# MercAp_PCB.net
KiCad netlist of a schematic drawn in Altium Designer
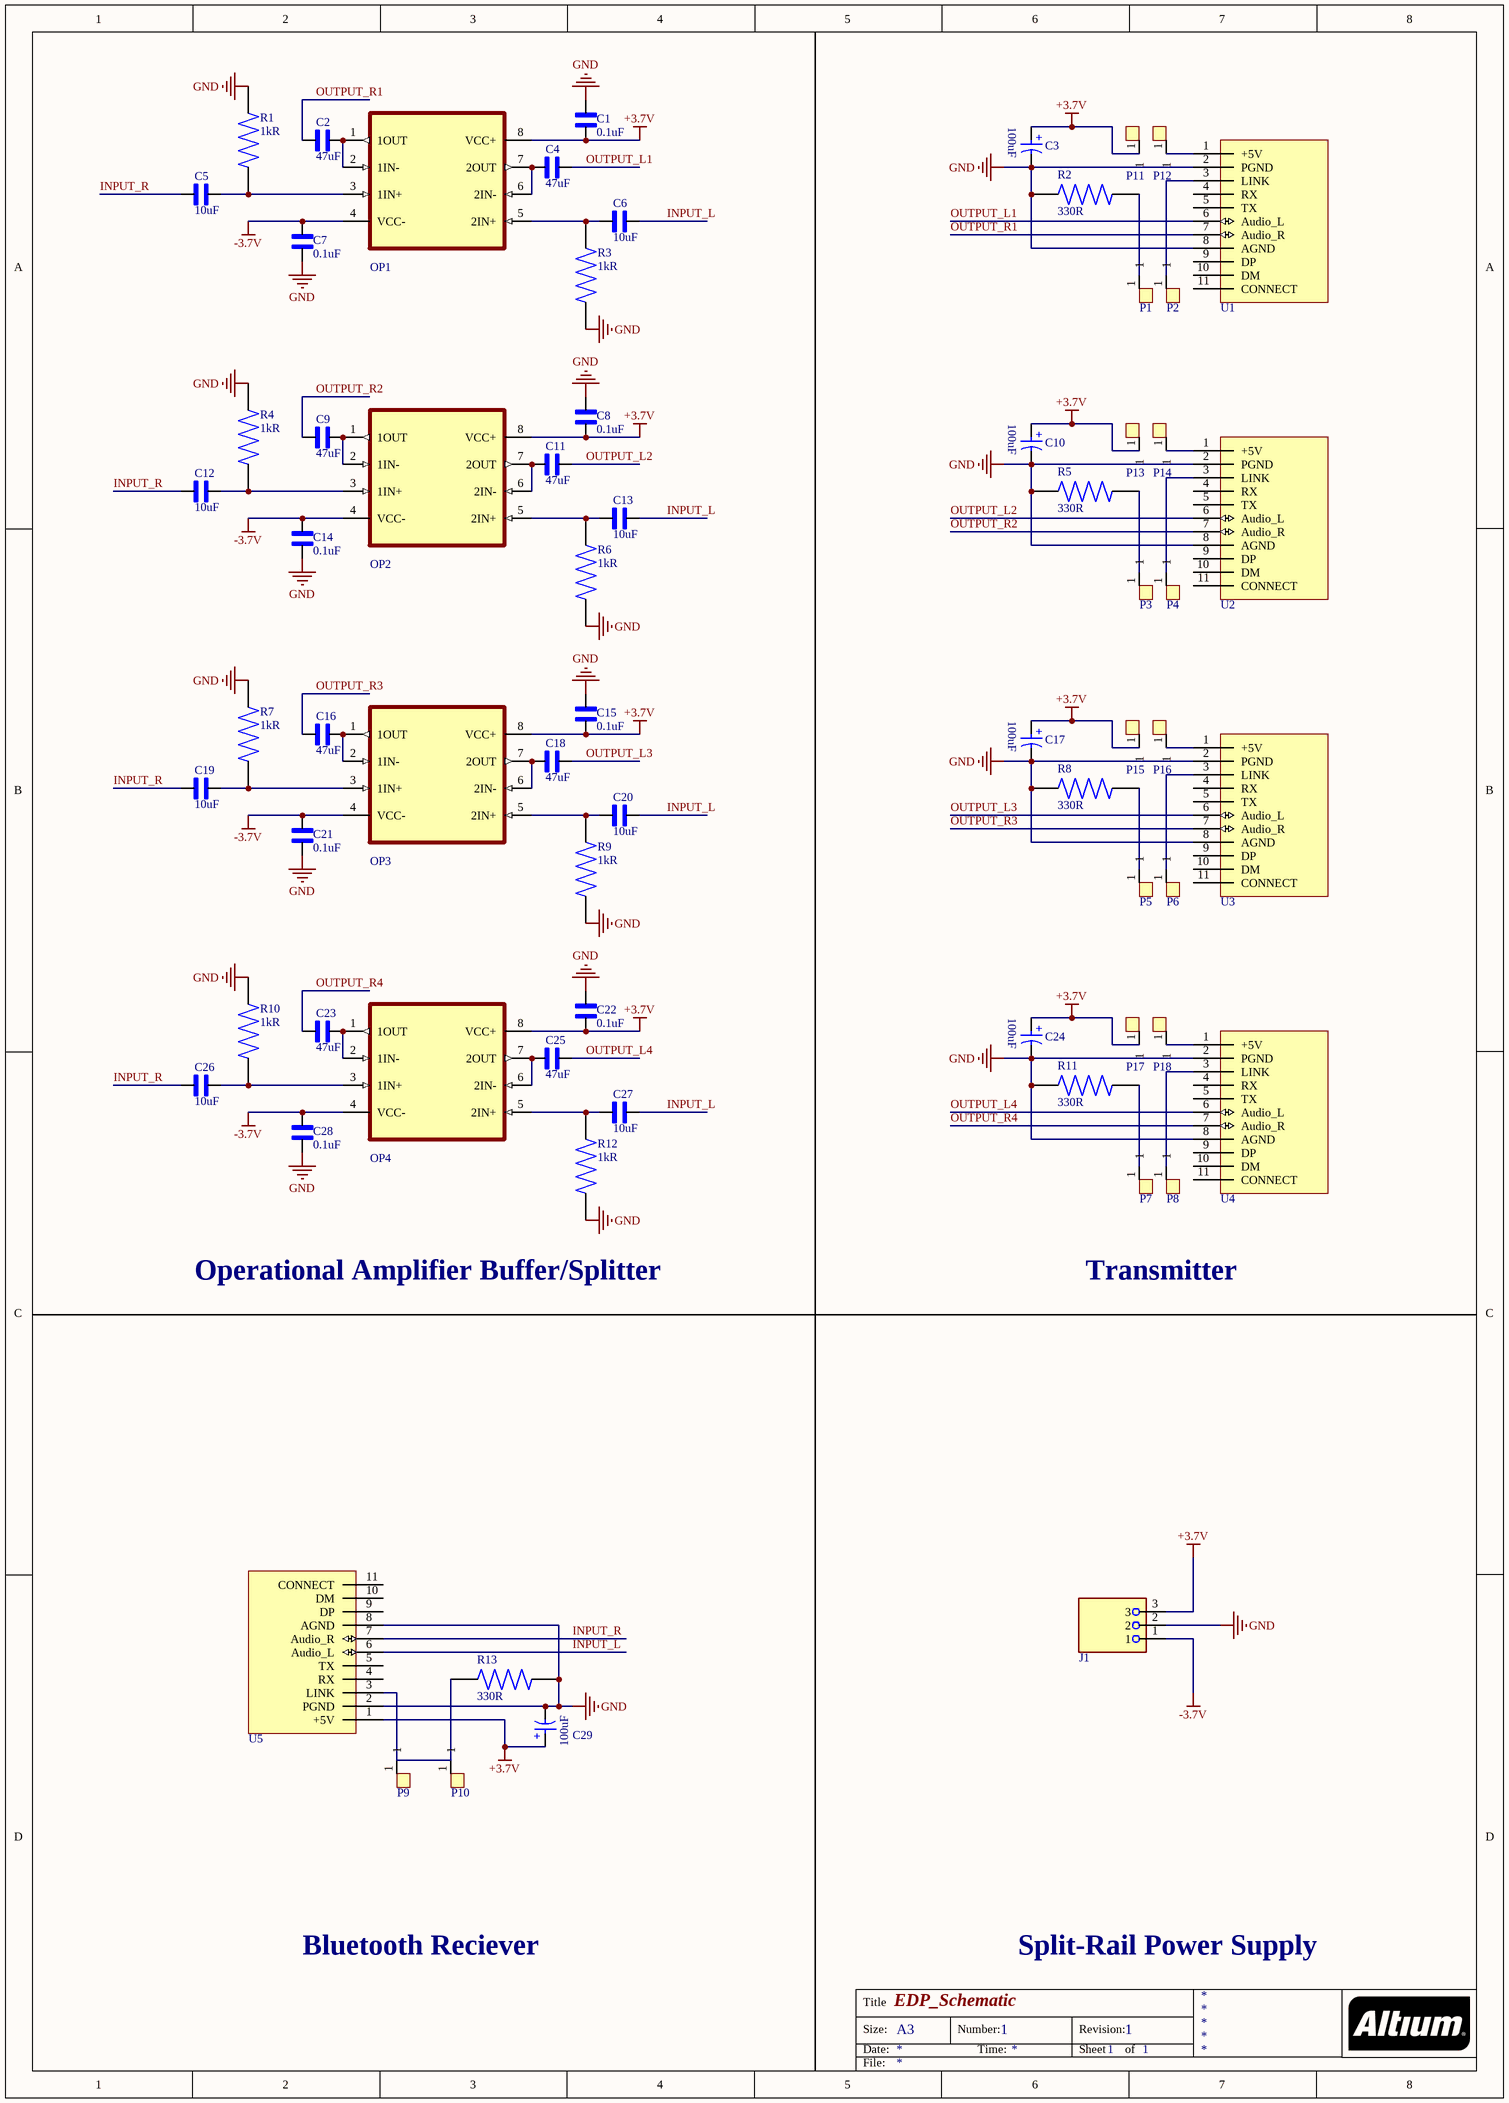
[diagram p0: MercAp PCB.SchDoc]

(export (version "E")
  (design (tool "Eeschema 10.0.6"))
  (components
    (comp (ref "C1")
      (value "0.1uF")
      (footprint "CAPC1005X55N")
      (fields
        (field (name "MANUFACTURER") "Samsung")
        (field (name "MANUFACTURER PART NUMBER") "CL05B104KP5NNNC")
      )
      (libsource (lib "EDP") (part "CL05B104KP5NNNC"))
    )
    (comp (ref "C2")
      (value "47uF")
      (footprint "CAPC2012X145N")
      (fields
        (field (name "MANUFACTURER") "Taiyo Yuden")
        (field (name "MANUFACTURER PART NUMBER") "JMK212BBJ476MG-T")
      )
      (libsource (lib "EDP") (part "JMK212BBJ476MG-T"))
    )
    (comp (ref "C3")
      (value "865080343009")
      (footprint "WCAP-ASLI_D6.3H5.5")
      (description "Aluminum Electrolytic Capacitor, Aluminum (wet)")
      (fields (field (name "MANUFACTURER") "Wurth Electronics"))
      (libsource (lib "EDP") (part "865080343009"))
    )
    (comp (ref "C4")
      (value "47uF")
      (footprint "CAPC2012X145N")
      (fields
        (field (name "MANUFACTURER") "Taiyo Yuden")
        (field (name "MANUFACTURER PART NUMBER") "JMK212BBJ476MG-T")
      )
      (libsource (lib "EDP") (part "JMK212BBJ476MG-T"))
    )
    (comp (ref "C5")
      (value "10uF")
      (footprint "CAPC2012X135N")
      (fields
        (field (name "MANUFACTURER") "Murata")
        (field (name "MANUFACTURER PART NUMBER") "GRM21BR61C106KE15K")
      )
      (libsource (lib "") (part "GRM21BR61C106KE15K_1"))
    )
    (comp (ref "C6")
      (value "10uF")
      (footprint "CAPC2012X135N")
      (fields
        (field (name "MANUFACTURER") "Murata")
        (field (name "MANUFACTURER PART NUMBER") "GRM21BR61C106KE15K")
      )
      (libsource (lib "EDP") (part "GRM21BR61C106KE15K"))
    )
    (comp (ref "C7")
      (value "0.1uF")
      (footprint "CAPC1005X55N")
      (fields
        (field (name "MANUFACTURER") "Samsung")
        (field (name "MANUFACTURER PART NUMBER") "CL05B104KP5NNNC")
      )
      (libsource (lib "EDP") (part "CL05B104KP5NNNC"))
    )
    (comp (ref "C8")
      (value "0.1uF")
      (footprint "CAPC1005X55N")
      (fields
        (field (name "MANUFACTURER") "Samsung")
        (field (name "MANUFACTURER PART NUMBER") "CL05B104KP5NNNC")
      )
      (libsource (lib "EDP") (part "CL05B104KP5NNNC"))
    )
    (comp (ref "C9")
      (value "47uF")
      (footprint "CAPC2012X145N")
      (fields
        (field (name "MANUFACTURER") "Taiyo Yuden")
        (field (name "MANUFACTURER PART NUMBER") "JMK212BBJ476MG-T")
      )
      (libsource (lib "EDP") (part "JMK212BBJ476MG-T"))
    )
    (comp (ref "C10")
      (value "865080343009")
      (footprint "WCAP-ASLI_D6.3H5.5")
      (description "Aluminum Electrolytic Capacitor, Aluminum (wet)")
      (fields (field (name "MANUFACTURER") "Wurth Electronics"))
      (libsource (lib "EDP") (part "865080343009"))
    )
    (comp (ref "C11")
      (value "47uF")
      (footprint "CAPC2012X145N")
      (fields
        (field (name "MANUFACTURER") "Taiyo Yuden")
        (field (name "MANUFACTURER PART NUMBER") "JMK212BBJ476MG-T")
      )
      (libsource (lib "EDP") (part "JMK212BBJ476MG-T"))
    )
    (comp (ref "C12")
      (value "10uF")
      (footprint "CAPC2012X135N")
      (fields
        (field (name "MANUFACTURER") "Murata")
        (field (name "MANUFACTURER PART NUMBER") "GRM21BR61C106KE15K")
      )
      (libsource (lib "") (part "GRM21BR61C106KE15K_1"))
    )
    (comp (ref "C13")
      (value "10uF")
      (footprint "CAPC2012X135N")
      (fields
        (field (name "MANUFACTURER") "Murata")
        (field (name "MANUFACTURER PART NUMBER") "GRM21BR61C106KE15K")
      )
      (libsource (lib "EDP") (part "GRM21BR61C106KE15K"))
    )
    (comp (ref "C14")
      (value "0.1uF")
      (footprint "CAPC1005X55N")
      (fields
        (field (name "MANUFACTURER") "Samsung")
        (field (name "MANUFACTURER PART NUMBER") "CL05B104KP5NNNC")
      )
      (libsource (lib "EDP") (part "CL05B104KP5NNNC"))
    )
    (comp (ref "C15")
      (value "0.1uF")
      (footprint "CAPC1005X55N")
      (fields
        (field (name "MANUFACTURER") "Samsung")
        (field (name "MANUFACTURER PART NUMBER") "CL05B104KP5NNNC")
      )
      (libsource (lib "EDP") (part "CL05B104KP5NNNC"))
    )
    (comp (ref "C16")
      (value "47uF")
      (footprint "CAPC2012X145N")
      (fields
        (field (name "MANUFACTURER") "Taiyo Yuden")
        (field (name "MANUFACTURER PART NUMBER") "JMK212BBJ476MG-T")
      )
      (libsource (lib "EDP") (part "JMK212BBJ476MG-T"))
    )
    (comp (ref "C17")
      (value "865080343009")
      (footprint "WCAP-ASLI_D6.3H5.5")
      (description "Aluminum Electrolytic Capacitor, Aluminum (wet)")
      (fields (field (name "MANUFACTURER") "Wurth Electronics"))
      (libsource (lib "EDP") (part "865080343009"))
    )
    (comp (ref "C18")
      (value "47uF")
      (footprint "CAPC2012X145N")
      (fields
        (field (name "MANUFACTURER") "Taiyo Yuden")
        (field (name "MANUFACTURER PART NUMBER") "JMK212BBJ476MG-T")
      )
      (libsource (lib "EDP") (part "JMK212BBJ476MG-T"))
    )
    (comp (ref "C19")
      (value "10uF")
      (footprint "CAPC2012X135N")
      (fields
        (field (name "MANUFACTURER") "Murata")
        (field (name "MANUFACTURER PART NUMBER") "GRM21BR61C106KE15K")
      )
      (libsource (lib "") (part "GRM21BR61C106KE15K_1"))
    )
    (comp (ref "C20")
      (value "10uF")
      (footprint "CAPC2012X135N")
      (fields
        (field (name "MANUFACTURER") "Murata")
        (field (name "MANUFACTURER PART NUMBER") "GRM21BR61C106KE15K")
      )
      (libsource (lib "EDP") (part "GRM21BR61C106KE15K"))
    )
    (comp (ref "C21")
      (value "0.1uF")
      (footprint "CAPC1005X55N")
      (fields
        (field (name "MANUFACTURER") "Samsung")
        (field (name "MANUFACTURER PART NUMBER") "CL05B104KP5NNNC")
      )
      (libsource (lib "EDP") (part "CL05B104KP5NNNC"))
    )
    (comp (ref "C22")
      (value "0.1uF")
      (footprint "CAPC1005X55N")
      (fields
        (field (name "MANUFACTURER") "Samsung")
        (field (name "MANUFACTURER PART NUMBER") "CL05B104KP5NNNC")
      )
      (libsource (lib "EDP") (part "CL05B104KP5NNNC"))
    )
    (comp (ref "C23")
      (value "47uF")
      (footprint "CAPC2012X145N")
      (fields
        (field (name "MANUFACTURER") "Taiyo Yuden")
        (field (name "MANUFACTURER PART NUMBER") "JMK212BBJ476MG-T")
      )
      (libsource (lib "EDP") (part "JMK212BBJ476MG-T"))
    )
    (comp (ref "C24")
      (value "865080343009")
      (footprint "WCAP-ASLI_D6.3H5.5")
      (description "Aluminum Electrolytic Capacitor, Aluminum (wet)")
      (fields (field (name "MANUFACTURER") "Wurth Electronics"))
      (libsource (lib "EDP") (part "865080343009"))
    )
    (comp (ref "C25")
      (value "47uF")
      (footprint "CAPC2012X145N")
      (fields
        (field (name "MANUFACTURER") "Taiyo Yuden")
        (field (name "MANUFACTURER PART NUMBER") "JMK212BBJ476MG-T")
      )
      (libsource (lib "EDP") (part "JMK212BBJ476MG-T"))
    )
    (comp (ref "C26")
      (value "10uF")
      (footprint "CAPC2012X135N")
      (fields
        (field (name "MANUFACTURER") "Murata")
        (field (name "MANUFACTURER PART NUMBER") "GRM21BR61C106KE15K")
      )
      (libsource (lib "") (part "GRM21BR61C106KE15K_1"))
    )
    (comp (ref "C27")
      (value "10uF")
      (footprint "CAPC2012X135N")
      (fields
        (field (name "MANUFACTURER") "Murata")
        (field (name "MANUFACTURER PART NUMBER") "GRM21BR61C106KE15K")
      )
      (libsource (lib "EDP") (part "GRM21BR61C106KE15K"))
    )
    (comp (ref "C28")
      (value "0.1uF")
      (footprint "CAPC1005X55N")
      (fields
        (field (name "MANUFACTURER") "Samsung")
        (field (name "MANUFACTURER PART NUMBER") "CL05B104KP5NNNC")
      )
      (libsource (lib "EDP") (part "CL05B104KP5NNNC"))
    )
    (comp (ref "C29")
      (value "865080343009")
      (footprint "WCAP-ASLI_D6.3H5.5")
      (description "Aluminum Electrolytic Capacitor, Aluminum (wet)")
      (fields (field (name "MANUFACTURER") "Wurth Electronics"))
      (libsource (lib "EDP") (part "865080343009"))
    )
    (comp (ref "J1")
      (value "1935174")
      (footprint "PHOENIX_1935174")
      (description "Barrier Strip Terminal Block, 17.5A, 1.5mm2, 1 Row(s), 1 Deck(s)")
      (fields (field (name "MANUFACTURER") "Phoenix Contact") (field (name "SAFETY APPROVAL") "UL"))
      (libsource (lib "EDP") (part "1935174"))
    )
    (comp (ref "OP1")
      (value "NE5532DR")
      (footprint "SOIC127P599X175-8N")
      (description "Operational Amplifier, 2 Func, 5000uV Offset-Max, BIPolar, PDSO8")
      (fields (field (name "MANUFACTURER") "Texas Instruments"))
      (libsource (lib "EDP") (part "NE5532DR"))
    )
    (comp (ref "OP2")
      (value "NE5532DR")
      (footprint "SOIC127P599X175-8N")
      (description "Operational Amplifier, 2 Func, 5000uV Offset-Max, BIPolar, PDSO8")
      (fields (field (name "MANUFACTURER") "Texas Instruments"))
      (libsource (lib "EDP") (part "NE5532DR"))
    )
    (comp (ref "OP3")
      (value "NE5532DR")
      (footprint "SOIC127P599X175-8N")
      (description "Operational Amplifier, 2 Func, 5000uV Offset-Max, BIPolar, PDSO8")
      (fields (field (name "MANUFACTURER") "Texas Instruments"))
      (libsource (lib "EDP") (part "NE5532DR"))
    )
    (comp (ref "OP4")
      (value "NE5532DR")
      (footprint "SOIC127P599X175-8N")
      (description "Operational Amplifier, 2 Func, 5000uV Offset-Max, BIPolar, PDSO8")
      (fields (field (name "MANUFACTURER") "Texas Instruments"))
      (libsource (lib "EDP") (part "NE5532DR"))
    )
    (comp (ref "P1")
      (value "LED_PAD")
      (footprint "SolderWirePad_1x01_SMD_5x10mm")
      (libsource (lib "EDP") (part "LED_PAD"))
    )
    (comp (ref "P2")
      (value "LED_PAD")
      (footprint "SolderWirePad_1x01_SMD_5x10mm")
      (libsource (lib "EDP") (part "LED_PAD"))
    )
    (comp (ref "P3")
      (value "LED_PAD")
      (footprint "SolderWirePad_1x01_SMD_5x10mm")
      (libsource (lib "EDP") (part "LED_PAD"))
    )
    (comp (ref "P4")
      (value "LED_PAD")
      (footprint "SolderWirePad_1x01_SMD_5x10mm")
      (libsource (lib "EDP") (part "LED_PAD"))
    )
    (comp (ref "P5")
      (value "LED_PAD")
      (footprint "SolderWirePad_1x01_SMD_5x10mm")
      (libsource (lib "EDP") (part "LED_PAD"))
    )
    (comp (ref "P6")
      (value "LED_PAD")
      (footprint "SolderWirePad_1x01_SMD_5x10mm")
      (libsource (lib "EDP") (part "LED_PAD"))
    )
    (comp (ref "P7")
      (value "LED_PAD")
      (footprint "SolderWirePad_1x01_SMD_5x10mm")
      (libsource (lib "EDP") (part "LED_PAD"))
    )
    (comp (ref "P8")
      (value "LED_PAD")
      (footprint "SolderWirePad_1x01_SMD_5x10mm")
      (libsource (lib "EDP") (part "LED_PAD"))
    )
    (comp (ref "P9")
      (value "LED_PAD")
      (footprint "SolderWirePad_1x01_SMD_5x10mm")
      (libsource (lib "EDP") (part "LED_PAD"))
    )
    (comp (ref "P10")
      (value "LED_PAD")
      (footprint "SolderWirePad_1x01_SMD_5x10mm")
      (libsource (lib "EDP") (part "LED_PAD"))
    )
    (comp (ref "P11")
      (value "LED_PAD")
      (footprint "SolderWirePad_1x01_SMD_5x10mm")
      (libsource (lib "") (part "LED_PAD_1"))
    )
    (comp (ref "P12")
      (value "LED_PAD")
      (footprint "SolderWirePad_1x01_SMD_5x10mm")
      (libsource (lib "") (part "LED_PAD_1"))
    )
    (comp (ref "P13")
      (value "LED_PAD")
      (footprint "SolderWirePad_1x01_SMD_5x10mm")
      (libsource (lib "") (part "LED_PAD_1"))
    )
    (comp (ref "P14")
      (value "LED_PAD")
      (footprint "SolderWirePad_1x01_SMD_5x10mm")
      (libsource (lib "") (part "LED_PAD_1"))
    )
    (comp (ref "P15")
      (value "LED_PAD")
      (footprint "SolderWirePad_1x01_SMD_5x10mm")
      (libsource (lib "") (part "LED_PAD_1"))
    )
    (comp (ref "P16")
      (value "LED_PAD")
      (footprint "SolderWirePad_1x01_SMD_5x10mm")
      (libsource (lib "") (part "LED_PAD_1"))
    )
    (comp (ref "P17")
      (value "LED_PAD")
      (footprint "SolderWirePad_1x01_SMD_5x10mm")
      (libsource (lib "") (part "LED_PAD_1"))
    )
    (comp (ref "P18")
      (value "LED_PAD")
      (footprint "SolderWirePad_1x01_SMD_5x10mm")
      (libsource (lib "") (part "LED_PAD_1"))
    )
    (comp (ref "R1")
      (value "1kR")
      (footprint "RESC1508X55N")
      (fields
        (field (name "MANUFACTURER") "Stackpole Electronics")
        (field (name "MANUFACTURER PART NUMBER") "RMCF0603FT1K00")
        (field (name "TOLERANCE") "1%")
      )
      (libsource (lib "EDP") (part "RMCF0603FT1K00"))
    )
    (comp (ref "R2")
      (value "330R")
      (footprint "RESC1608X55N")
      (fields
        (field (name "MANUFACTURER") "Yageo")
        (field (name "MANUFACTURER PART NUMBER") "RC0603JR-07330RL")
        (field (name "TOLERANCE") "5%")
      )
      (libsource (lib "EDP") (part "RC0603JR-07330RL"))
    )
    (comp (ref "R3")
      (value "1kR")
      (footprint "RESC1508X55N")
      (fields
        (field (name "MANUFACTURER") "Stackpole Electronics")
        (field (name "MANUFACTURER PART NUMBER") "RMCF0603FT1K00")
        (field (name "TOLERANCE") "1%")
      )
      (libsource (lib "EDP") (part "RMCF0603FT1K00"))
    )
    (comp (ref "R4")
      (value "1kR")
      (footprint "RESC1508X55N")
      (fields
        (field (name "MANUFACTURER") "Stackpole Electronics")
        (field (name "MANUFACTURER PART NUMBER") "RMCF0603FT1K00")
        (field (name "TOLERANCE") "1%")
      )
      (libsource (lib "EDP") (part "RMCF0603FT1K00"))
    )
    (comp (ref "R5")
      (value "330R")
      (footprint "RESC1608X55N")
      (fields
        (field (name "MANUFACTURER") "Yageo")
        (field (name "MANUFACTURER PART NUMBER") "RC0603JR-07330RL")
        (field (name "TOLERANCE") "5%")
      )
      (libsource (lib "EDP") (part "RC0603JR-07330RL"))
    )
    (comp (ref "R6")
      (value "1kR")
      (footprint "RESC1508X55N")
      (fields
        (field (name "MANUFACTURER") "Stackpole Electronics")
        (field (name "MANUFACTURER PART NUMBER") "RMCF0603FT1K00")
        (field (name "TOLERANCE") "1%")
      )
      (libsource (lib "EDP") (part "RMCF0603FT1K00"))
    )
    (comp (ref "R7")
      (value "1kR")
      (footprint "RESC1508X55N")
      (fields
        (field (name "MANUFACTURER") "Stackpole Electronics")
        (field (name "MANUFACTURER PART NUMBER") "RMCF0603FT1K00")
        (field (name "TOLERANCE") "1%")
      )
      (libsource (lib "EDP") (part "RMCF0603FT1K00"))
    )
    (comp (ref "R8")
      (value "330R")
      (footprint "RESC1608X55N")
      (fields
        (field (name "MANUFACTURER") "Yageo")
        (field (name "MANUFACTURER PART NUMBER") "RC0603JR-07330RL")
        (field (name "TOLERANCE") "5%")
      )
      (libsource (lib "EDP") (part "RC0603JR-07330RL"))
    )
    (comp (ref "R9")
      (value "1kR")
      (footprint "RESC1508X55N")
      (fields
        (field (name "MANUFACTURER") "Stackpole Electronics")
        (field (name "MANUFACTURER PART NUMBER") "RMCF0603FT1K00")
        (field (name "TOLERANCE") "1%")
      )
      (libsource (lib "EDP") (part "RMCF0603FT1K00"))
    )
    (comp (ref "R10")
      (value "1kR")
      (footprint "RESC1508X55N")
      (fields
        (field (name "MANUFACTURER") "Stackpole Electronics")
        (field (name "MANUFACTURER PART NUMBER") "RMCF0603FT1K00")
        (field (name "TOLERANCE") "1%")
      )
      (libsource (lib "EDP") (part "RMCF0603FT1K00"))
    )
    (comp (ref "R11")
      (value "330R")
      (footprint "RESC1608X55N")
      (fields
        (field (name "MANUFACTURER") "Yageo")
        (field (name "MANUFACTURER PART NUMBER") "RC0603JR-07330RL")
        (field (name "TOLERANCE") "5%")
      )
      (libsource (lib "EDP") (part "RC0603JR-07330RL"))
    )
    (comp (ref "R12")
      (value "1kR")
      (footprint "RESC1508X55N")
      (fields
        (field (name "MANUFACTURER") "Stackpole Electronics")
        (field (name "MANUFACTURER PART NUMBER") "RMCF0603FT1K00")
        (field (name "TOLERANCE") "1%")
      )
      (libsource (lib "EDP") (part "RMCF0603FT1K00"))
    )
    (comp (ref "R13")
      (value "330R")
      (footprint "RESC1608X55N")
      (fields
        (field (name "MANUFACTURER") "Yageo")
        (field (name "MANUFACTURER PART NUMBER") "RC0603JR-07330RL")
        (field (name "TOLERANCE") "5%")
      )
      (libsource (lib "EDP") (part "RC0603JR-07330RL"))
    )
    (comp (ref "U1")
      (value "KCX_BT_v1.4")
      (footprint "kcx_bt_emitter_foot")
      (libsource (lib "EDP") (part "KCX_BT_v1.4"))
    )
    (comp (ref "U2")
      (value "KCX_BT_v1.4")
      (footprint "kcx_bt_emitter_foot")
      (libsource (lib "EDP") (part "KCX_BT_v1.4"))
    )
    (comp (ref "U3")
      (value "KCX_BT_v1.4")
      (footprint "kcx_bt_emitter_foot")
      (libsource (lib "EDP") (part "KCX_BT_v1.4"))
    )
    (comp (ref "U4")
      (value "KCX_BT_v1.4")
      (footprint "kcx_bt_emitter_foot")
      (libsource (lib "EDP") (part "KCX_BT_v1.4"))
    )
    (comp (ref "U5")
      (value "KCX_BT_v1.4")
      (footprint "kcx_bt_emitter_foot")
      (libsource (lib "") (part "KCX_BT_v1.4_1"))
    )
  )
  (nets
    (net (code "1") (name "+3.7V") (class "Default")
      (node (ref "C1") (pin "1") (pinfunction "1_1") (pintype "passive"))
      (node (ref "C10") (pin "1") (pinfunction "P_1") (pintype "passive"))
      (node (ref "C15") (pin "1") (pinfunction "1_1") (pintype "passive"))
      (node (ref "C17") (pin "1") (pinfunction "P_1") (pintype "passive"))
      (node (ref "C22") (pin "1") (pinfunction "1_1") (pintype "passive"))
      (node (ref "C24") (pin "1") (pinfunction "P_1") (pintype "passive"))
      (node (ref "C29") (pin "1") (pinfunction "P_1") (pintype "passive"))
      (node (ref "C3") (pin "1") (pinfunction "P_1") (pintype "passive"))
      (node (ref "C8") (pin "1") (pinfunction "1_1") (pintype "passive"))
      (node (ref "J1") (pin "3") (pinfunction "3_3") (pintype "passive"))
      (node (ref "OP1") (pin "8") (pinfunction "VCC+_8") (pintype "power_in"))
      (node (ref "OP2") (pin "8") (pinfunction "VCC+_8") (pintype "power_in"))
      (node (ref "OP3") (pin "8") (pinfunction "VCC+_8") (pintype "power_in"))
      (node (ref "OP4") (pin "8") (pinfunction "VCC+_8") (pintype "power_in"))
      (node (ref "U5") (pin "1") (pinfunction "+5V_1") (pintype "power_in"))
    )
    (net (code "2") (name "-3.7V") (class "Default")
      (node (ref "C14") (pin "2") (pinfunction "2_2") (pintype "passive"))
      (node (ref "C21") (pin "2") (pinfunction "2_2") (pintype "passive"))
      (node (ref "C28") (pin "2") (pinfunction "2_2") (pintype "passive"))
      (node (ref "C7") (pin "2") (pinfunction "2_2") (pintype "passive"))
      (node (ref "J1") (pin "1") (pinfunction "1_1") (pintype "passive"))
      (node (ref "OP1") (pin "4") (pinfunction "VCC-_4") (pintype "power_in"))
      (node (ref "OP2") (pin "4") (pinfunction "VCC-_4") (pintype "power_in"))
      (node (ref "OP3") (pin "4") (pinfunction "VCC-_4") (pintype "power_in"))
      (node (ref "OP4") (pin "4") (pinfunction "VCC-_4") (pintype "power_in"))
    )
    (net (code "3") (name "/INPUT_L") (class "Default")
      (node (ref "C13") (pin "1") (pinfunction "1_1") (pintype "passive"))
      (node (ref "C20") (pin "1") (pinfunction "1_1") (pintype "passive"))
      (node (ref "C27") (pin "1") (pinfunction "1_1") (pintype "passive"))
      (node (ref "C6") (pin "1") (pinfunction "1_1") (pintype "passive"))
      (node (ref "U5") (pin "6") (pinfunction "Audio_L_6") (pintype "bidirectional"))
    )
    (net (code "4") (name "/INPUT_R") (class "Default")
      (node (ref "C12") (pin "1") (pinfunction "1_1") (pintype "passive"))
      (node (ref "C19") (pin "1") (pinfunction "1_1") (pintype "passive"))
      (node (ref "C26") (pin "1") (pinfunction "1_1") (pintype "passive"))
      (node (ref "C5") (pin "1") (pinfunction "1_1") (pintype "passive"))
      (node (ref "U5") (pin "7") (pinfunction "Audio_R_7") (pintype "bidirectional"))
    )
    (net (code "5") (name "/OUTPUT_L1") (class "Default")
      (node (ref "C4") (pin "2") (pinfunction "2_2") (pintype "passive"))
      (node (ref "U1") (pin "6") (pinfunction "Audio_L_6") (pintype "bidirectional"))
    )
    (net (code "6") (name "/OUTPUT_L2") (class "Default")
      (node (ref "C11") (pin "2") (pinfunction "2_2") (pintype "passive"))
      (node (ref "U2") (pin "6") (pinfunction "Audio_L_6") (pintype "bidirectional"))
    )
    (net (code "7") (name "/OUTPUT_L3") (class "Default")
      (node (ref "C18") (pin "2") (pinfunction "2_2") (pintype "passive"))
      (node (ref "U3") (pin "6") (pinfunction "Audio_L_6") (pintype "bidirectional"))
    )
    (net (code "8") (name "/OUTPUT_L4") (class "Default")
      (node (ref "C25") (pin "2") (pinfunction "2_2") (pintype "passive"))
      (node (ref "U4") (pin "6") (pinfunction "Audio_L_6") (pintype "bidirectional"))
    )
    (net (code "9") (name "/OUTPUT_R1") (class "Default")
      (node (ref "C2") (pin "1") (pinfunction "1_1") (pintype "passive"))
      (node (ref "U1") (pin "7") (pinfunction "Audio_R_7") (pintype "bidirectional"))
    )
    (net (code "10") (name "/OUTPUT_R2") (class "Default")
      (node (ref "C9") (pin "1") (pinfunction "1_1") (pintype "passive"))
      (node (ref "U2") (pin "7") (pinfunction "Audio_R_7") (pintype "bidirectional"))
    )
    (net (code "11") (name "/OUTPUT_R3") (class "Default")
      (node (ref "C16") (pin "1") (pinfunction "1_1") (pintype "passive"))
      (node (ref "U3") (pin "7") (pinfunction "Audio_R_7") (pintype "bidirectional"))
    )
    (net (code "12") (name "/OUTPUT_R4") (class "Default")
      (node (ref "C23") (pin "1") (pinfunction "1_1") (pintype "passive"))
      (node (ref "U4") (pin "7") (pinfunction "Audio_R_7") (pintype "bidirectional"))
    )
    (net (code "13") (name "GND") (class "Default")
      (node (ref "C1") (pin "2") (pinfunction "2_2") (pintype "passive"))
      (node (ref "C10") (pin "2") (pinfunction "N_2") (pintype "passive"))
      (node (ref "C14") (pin "1") (pinfunction "1_1") (pintype "passive"))
      (node (ref "C15") (pin "2") (pinfunction "2_2") (pintype "passive"))
      (node (ref "C17") (pin "2") (pinfunction "N_2") (pintype "passive"))
      (node (ref "C21") (pin "1") (pinfunction "1_1") (pintype "passive"))
      (node (ref "C22") (pin "2") (pinfunction "2_2") (pintype "passive"))
      (node (ref "C24") (pin "2") (pinfunction "N_2") (pintype "passive"))
      (node (ref "C28") (pin "1") (pinfunction "1_1") (pintype "passive"))
      (node (ref "C29") (pin "2") (pinfunction "N_2") (pintype "passive"))
      (node (ref "C3") (pin "2") (pinfunction "N_2") (pintype "passive"))
      (node (ref "C7") (pin "1") (pinfunction "1_1") (pintype "passive"))
      (node (ref "C8") (pin "2") (pinfunction "2_2") (pintype "passive"))
      (node (ref "J1") (pin "2") (pinfunction "2_2") (pintype "passive"))
      (node (ref "R1") (pin "1") (pinfunction "1_1") (pintype "passive"))
      (node (ref "R10") (pin "1") (pinfunction "1_1") (pintype "passive"))
      (node (ref "R11") (pin "1") (pinfunction "1_1") (pintype "passive"))
      (node (ref "R12") (pin "1") (pinfunction "1_1") (pintype "passive"))
      (node (ref "R13") (pin "1") (pinfunction "1_1") (pintype "passive"))
      (node (ref "R2") (pin "1") (pinfunction "1_1") (pintype "passive"))
      (node (ref "R3") (pin "1") (pinfunction "1_1") (pintype "passive"))
      (node (ref "R4") (pin "1") (pinfunction "1_1") (pintype "passive"))
      (node (ref "R5") (pin "1") (pinfunction "1_1") (pintype "passive"))
      (node (ref "R6") (pin "1") (pinfunction "1_1") (pintype "passive"))
      (node (ref "R7") (pin "1") (pinfunction "1_1") (pintype "passive"))
      (node (ref "R8") (pin "1") (pinfunction "1_1") (pintype "passive"))
      (node (ref "R9") (pin "1") (pinfunction "1_1") (pintype "passive"))
      (node (ref "U1") (pin "2") (pinfunction "PGND_2") (pintype "power_in"))
      (node (ref "U1") (pin "8") (pinfunction "AGND_8") (pintype "power_in"))
      (node (ref "U2") (pin "2") (pinfunction "PGND_2") (pintype "power_in"))
      (node (ref "U2") (pin "8") (pinfunction "AGND_8") (pintype "power_in"))
      (node (ref "U3") (pin "2") (pinfunction "PGND_2") (pintype "power_in"))
      (node (ref "U3") (pin "8") (pinfunction "AGND_8") (pintype "power_in"))
      (node (ref "U4") (pin "2") (pinfunction "PGND_2") (pintype "power_in"))
      (node (ref "U4") (pin "8") (pinfunction "AGND_8") (pintype "power_in"))
      (node (ref "U5") (pin "2") (pinfunction "PGND_2") (pintype "power_in"))
      (node (ref "U5") (pin "8") (pinfunction "AGND_8") (pintype "power_in"))
    )
    (net (code "14") (name "Net-(OP1-1IN+)") (class "Default")
      (node (ref "C5") (pin "2") (pinfunction "2_2") (pintype "passive"))
      (node (ref "OP1") (pin "3") (pinfunction "1IN+_3") (pintype "input"))
      (node (ref "R1") (pin "2") (pinfunction "2_2") (pintype "passive"))
    )
    (net (code "15") (name "Net-(OP1-1IN-)") (class "Default")
      (node (ref "C2") (pin "2") (pinfunction "2_2") (pintype "passive"))
      (node (ref "OP1") (pin "1") (pinfunction "1OUT_1") (pintype "output"))
      (node (ref "OP1") (pin "2") (pinfunction "1IN-_2") (pintype "input"))
    )
    (net (code "16") (name "Net-(OP1-2IN+)") (class "Default")
      (node (ref "C6") (pin "2") (pinfunction "2_2") (pintype "passive"))
      (node (ref "OP1") (pin "5") (pinfunction "2IN+_5") (pintype "input"))
      (node (ref "R3") (pin "2") (pinfunction "2_2") (pintype "passive"))
    )
    (net (code "17") (name "Net-(OP1-2IN-)") (class "Default")
      (node (ref "C4") (pin "1") (pinfunction "1_1") (pintype "passive"))
      (node (ref "OP1") (pin "6") (pinfunction "2IN-_6") (pintype "input"))
      (node (ref "OP1") (pin "7") (pinfunction "2OUT_7") (pintype "output"))
    )
    (net (code "18") (name "Net-(OP2-1IN+)") (class "Default")
      (node (ref "C12") (pin "2") (pinfunction "2_2") (pintype "passive"))
      (node (ref "OP2") (pin "3") (pinfunction "1IN+_3") (pintype "input"))
      (node (ref "R4") (pin "2") (pinfunction "2_2") (pintype "passive"))
    )
    (net (code "19") (name "Net-(OP2-1IN-)") (class "Default")
      (node (ref "C9") (pin "2") (pinfunction "2_2") (pintype "passive"))
      (node (ref "OP2") (pin "1") (pinfunction "1OUT_1") (pintype "output"))
      (node (ref "OP2") (pin "2") (pinfunction "1IN-_2") (pintype "input"))
    )
    (net (code "20") (name "Net-(OP2-2IN+)") (class "Default")
      (node (ref "C13") (pin "2") (pinfunction "2_2") (pintype "passive"))
      (node (ref "OP2") (pin "5") (pinfunction "2IN+_5") (pintype "input"))
      (node (ref "R6") (pin "2") (pinfunction "2_2") (pintype "passive"))
    )
    (net (code "21") (name "Net-(OP2-2IN-)") (class "Default")
      (node (ref "C11") (pin "1") (pinfunction "1_1") (pintype "passive"))
      (node (ref "OP2") (pin "6") (pinfunction "2IN-_6") (pintype "input"))
      (node (ref "OP2") (pin "7") (pinfunction "2OUT_7") (pintype "output"))
    )
    (net (code "22") (name "Net-(OP3-1IN+)") (class "Default")
      (node (ref "C19") (pin "2") (pinfunction "2_2") (pintype "passive"))
      (node (ref "OP3") (pin "3") (pinfunction "1IN+_3") (pintype "input"))
      (node (ref "R7") (pin "2") (pinfunction "2_2") (pintype "passive"))
    )
    (net (code "23") (name "Net-(OP3-1IN-)") (class "Default")
      (node (ref "C16") (pin "2") (pinfunction "2_2") (pintype "passive"))
      (node (ref "OP3") (pin "1") (pinfunction "1OUT_1") (pintype "output"))
      (node (ref "OP3") (pin "2") (pinfunction "1IN-_2") (pintype "input"))
    )
    (net (code "24") (name "Net-(OP3-2IN+)") (class "Default")
      (node (ref "C20") (pin "2") (pinfunction "2_2") (pintype "passive"))
      (node (ref "OP3") (pin "5") (pinfunction "2IN+_5") (pintype "input"))
      (node (ref "R9") (pin "2") (pinfunction "2_2") (pintype "passive"))
    )
    (net (code "25") (name "Net-(OP3-2IN-)") (class "Default")
      (node (ref "C18") (pin "1") (pinfunction "1_1") (pintype "passive"))
      (node (ref "OP3") (pin "6") (pinfunction "2IN-_6") (pintype "input"))
      (node (ref "OP3") (pin "7") (pinfunction "2OUT_7") (pintype "output"))
    )
    (net (code "26") (name "Net-(OP4-1IN+)") (class "Default")
      (node (ref "C26") (pin "2") (pinfunction "2_2") (pintype "passive"))
      (node (ref "OP4") (pin "3") (pinfunction "1IN+_3") (pintype "input"))
      (node (ref "R10") (pin "2") (pinfunction "2_2") (pintype "passive"))
    )
    (net (code "27") (name "Net-(OP4-1IN-)") (class "Default")
      (node (ref "C23") (pin "2") (pinfunction "2_2") (pintype "passive"))
      (node (ref "OP4") (pin "1") (pinfunction "1OUT_1") (pintype "output"))
      (node (ref "OP4") (pin "2") (pinfunction "1IN-_2") (pintype "input"))
    )
    (net (code "28") (name "Net-(OP4-2IN+)") (class "Default")
      (node (ref "C27") (pin "2") (pinfunction "2_2") (pintype "passive"))
      (node (ref "OP4") (pin "5") (pinfunction "2IN+_5") (pintype "input"))
      (node (ref "R12") (pin "2") (pinfunction "2_2") (pintype "passive"))
    )
    (net (code "29") (name "Net-(OP4-2IN-)") (class "Default")
      (node (ref "C25") (pin "1") (pinfunction "1_1") (pintype "passive"))
      (node (ref "OP4") (pin "6") (pinfunction "2IN-_6") (pintype "input"))
      (node (ref "OP4") (pin "7") (pinfunction "2OUT_7") (pintype "output"))
    )
    (net (code "30") (name "Net-(U5-LINK)") (class "Default")
      (node (ref "R13") (pin "2") (pinfunction "2_2") (pintype "passive"))
      (node (ref "U5") (pin "3") (pinfunction "LINK_3") (pintype "passive"))
    )
    (net (code "31") (name "unconnected-(P1-Pad1)") (class "Default")
      (node (ref "P1") (pin "1") (pinfunction "1_1") (pintype "passive"))
    )
    (net (code "32") (name "unconnected-(P2-Pad1)") (class "Default")
      (node (ref "P2") (pin "1") (pinfunction "1_1") (pintype "passive"))
    )
    (net (code "33") (name "unconnected-(P3-Pad1)") (class "Default")
      (node (ref "P3") (pin "1") (pinfunction "1_1") (pintype "passive"))
    )
    (net (code "34") (name "unconnected-(P4-Pad1)") (class "Default")
      (node (ref "P4") (pin "1") (pinfunction "1_1") (pintype "passive"))
    )
    (net (code "35") (name "unconnected-(P5-Pad1)") (class "Default")
      (node (ref "P5") (pin "1") (pinfunction "1_1") (pintype "passive"))
    )
    (net (code "36") (name "unconnected-(P6-Pad1)") (class "Default")
      (node (ref "P6") (pin "1") (pinfunction "1_1") (pintype "passive"))
    )
    (net (code "37") (name "unconnected-(P7-Pad1)") (class "Default")
      (node (ref "P7") (pin "1") (pinfunction "1_1") (pintype "passive"))
    )
    (net (code "38") (name "unconnected-(P8-Pad1)") (class "Default")
      (node (ref "P8") (pin "1") (pinfunction "1_1") (pintype "passive"))
    )
    (net (code "39") (name "unconnected-(P9-Pad1)") (class "Default")
      (node (ref "P9") (pin "1") (pinfunction "1_1") (pintype "passive"))
    )
    (net (code "40") (name "unconnected-(P10-Pad1)") (class "Default")
      (node (ref "P10") (pin "1") (pinfunction "1_1") (pintype "passive"))
    )
    (net (code "41") (name "unconnected-(P11-Pad1)") (class "Default")
      (node (ref "P11") (pin "1") (pinfunction "1_1") (pintype "passive"))
    )
    (net (code "42") (name "unconnected-(P12-Pad1)") (class "Default")
      (node (ref "P12") (pin "1") (pinfunction "1_1") (pintype "passive"))
    )
    (net (code "43") (name "unconnected-(P13-Pad1)") (class "Default")
      (node (ref "P13") (pin "1") (pinfunction "1_1") (pintype "passive"))
    )
    (net (code "44") (name "unconnected-(P14-Pad1)") (class "Default")
      (node (ref "P14") (pin "1") (pinfunction "1_1") (pintype "passive"))
    )
    (net (code "45") (name "unconnected-(P15-Pad1)") (class "Default")
      (node (ref "P15") (pin "1") (pinfunction "1_1") (pintype "passive"))
    )
    (net (code "46") (name "unconnected-(P16-Pad1)") (class "Default")
      (node (ref "P16") (pin "1") (pinfunction "1_1") (pintype "passive"))
    )
    (net (code "47") (name "unconnected-(P17-Pad1)") (class "Default")
      (node (ref "P17") (pin "1") (pinfunction "1_1") (pintype "passive"))
    )
    (net (code "48") (name "unconnected-(P18-Pad1)") (class "Default")
      (node (ref "P18") (pin "1") (pinfunction "1_1") (pintype "passive"))
    )
    (net (code "49") (name "unconnected-(R2-Pad2)") (class "Default")
      (node (ref "R2") (pin "2") (pinfunction "2_2") (pintype "passive"))
    )
    (net (code "50") (name "unconnected-(R5-Pad2)") (class "Default")
      (node (ref "R5") (pin "2") (pinfunction "2_2") (pintype "passive"))
    )
    (net (code "51") (name "unconnected-(R8-Pad2)") (class "Default")
      (node (ref "R8") (pin "2") (pinfunction "2_2") (pintype "passive"))
    )
    (net (code "52") (name "unconnected-(R11-Pad2)") (class "Default")
      (node (ref "R11") (pin "2") (pinfunction "2_2") (pintype "passive"))
    )
    (net (code "53") (name "unconnected-(U1-+5V-Pad1)") (class "Default")
      (node (ref "U1") (pin "1") (pinfunction "+5V_1") (pintype "power_in"))
    )
    (net (code "54") (name "unconnected-(U1-CONNECT-Pad11)") (class "Default")
      (node (ref "U1") (pin "11") (pinfunction "CONNECT_11") (pintype "passive"))
    )
    (net (code "55") (name "unconnected-(U1-DM-Pad10)") (class "Default")
      (node (ref "U1") (pin "10") (pinfunction "DM_10") (pintype "passive"))
    )
    (net (code "56") (name "unconnected-(U1-DP-Pad9)") (class "Default")
      (node (ref "U1") (pin "9") (pinfunction "DP_9") (pintype "passive"))
    )
    (net (code "57") (name "unconnected-(U1-LINK-Pad3)") (class "Default")
      (node (ref "U1") (pin "3") (pinfunction "LINK_3") (pintype "passive"))
    )
    (net (code "58") (name "unconnected-(U1-RX-Pad4)") (class "Default")
      (node (ref "U1") (pin "4") (pinfunction "RX_4") (pintype "passive"))
    )
    (net (code "59") (name "unconnected-(U1-TX-Pad5)") (class "Default")
      (node (ref "U1") (pin "5") (pinfunction "TX_5") (pintype "passive"))
    )
    (net (code "60") (name "unconnected-(U2-+5V-Pad1)") (class "Default")
      (node (ref "U2") (pin "1") (pinfunction "+5V_1") (pintype "power_in"))
    )
    (net (code "61") (name "unconnected-(U2-CONNECT-Pad11)") (class "Default")
      (node (ref "U2") (pin "11") (pinfunction "CONNECT_11") (pintype "passive"))
    )
    (net (code "62") (name "unconnected-(U2-DM-Pad10)") (class "Default")
      (node (ref "U2") (pin "10") (pinfunction "DM_10") (pintype "passive"))
    )
    (net (code "63") (name "unconnected-(U2-DP-Pad9)") (class "Default")
      (node (ref "U2") (pin "9") (pinfunction "DP_9") (pintype "passive"))
    )
    (net (code "64") (name "unconnected-(U2-LINK-Pad3)") (class "Default")
      (node (ref "U2") (pin "3") (pinfunction "LINK_3") (pintype "passive"))
    )
    (net (code "65") (name "unconnected-(U2-RX-Pad4)") (class "Default")
      (node (ref "U2") (pin "4") (pinfunction "RX_4") (pintype "passive"))
    )
    (net (code "66") (name "unconnected-(U2-TX-Pad5)") (class "Default")
      (node (ref "U2") (pin "5") (pinfunction "TX_5") (pintype "passive"))
    )
    (net (code "67") (name "unconnected-(U3-+5V-Pad1)") (class "Default")
      (node (ref "U3") (pin "1") (pinfunction "+5V_1") (pintype "power_in"))
    )
    (net (code "68") (name "unconnected-(U3-CONNECT-Pad11)") (class "Default")
      (node (ref "U3") (pin "11") (pinfunction "CONNECT_11") (pintype "passive"))
    )
    (net (code "69") (name "unconnected-(U3-DM-Pad10)") (class "Default")
      (node (ref "U3") (pin "10") (pinfunction "DM_10") (pintype "passive"))
    )
    (net (code "70") (name "unconnected-(U3-DP-Pad9)") (class "Default")
      (node (ref "U3") (pin "9") (pinfunction "DP_9") (pintype "passive"))
    )
    (net (code "71") (name "unconnected-(U3-LINK-Pad3)") (class "Default")
      (node (ref "U3") (pin "3") (pinfunction "LINK_3") (pintype "passive"))
    )
    (net (code "72") (name "unconnected-(U3-RX-Pad4)") (class "Default")
      (node (ref "U3") (pin "4") (pinfunction "RX_4") (pintype "passive"))
    )
    (net (code "73") (name "unconnected-(U3-TX-Pad5)") (class "Default")
      (node (ref "U3") (pin "5") (pinfunction "TX_5") (pintype "passive"))
    )
    (net (code "74") (name "unconnected-(U4-+5V-Pad1)") (class "Default")
      (node (ref "U4") (pin "1") (pinfunction "+5V_1") (pintype "power_in"))
    )
    (net (code "75") (name "unconnected-(U4-CONNECT-Pad11)") (class "Default")
      (node (ref "U4") (pin "11") (pinfunction "CONNECT_11") (pintype "passive"))
    )
    (net (code "76") (name "unconnected-(U4-DM-Pad10)") (class "Default")
      (node (ref "U4") (pin "10") (pinfunction "DM_10") (pintype "passive"))
    )
    (net (code "77") (name "unconnected-(U4-DP-Pad9)") (class "Default")
      (node (ref "U4") (pin "9") (pinfunction "DP_9") (pintype "passive"))
    )
    (net (code "78") (name "unconnected-(U4-LINK-Pad3)") (class "Default")
      (node (ref "U4") (pin "3") (pinfunction "LINK_3") (pintype "passive"))
    )
    (net (code "79") (name "unconnected-(U4-RX-Pad4)") (class "Default")
      (node (ref "U4") (pin "4") (pinfunction "RX_4") (pintype "passive"))
    )
    (net (code "80") (name "unconnected-(U4-TX-Pad5)") (class "Default")
      (node (ref "U4") (pin "5") (pinfunction "TX_5") (pintype "passive"))
    )
    (net (code "81") (name "unconnected-(U5-CONNECT-Pad11)") (class "Default")
      (node (ref "U5") (pin "11") (pinfunction "CONNECT_11") (pintype "passive"))
    )
    (net (code "82") (name "unconnected-(U5-DM-Pad10)") (class "Default")
      (node (ref "U5") (pin "10") (pinfunction "DM_10") (pintype "passive"))
    )
    (net (code "83") (name "unconnected-(U5-DP-Pad9)") (class "Default")
      (node (ref "U5") (pin "9") (pinfunction "DP_9") (pintype "passive"))
    )
    (net (code "84") (name "unconnected-(U5-RX-Pad4)") (class "Default")
      (node (ref "U5") (pin "4") (pinfunction "RX_4") (pintype "passive"))
    )
    (net (code "85") (name "unconnected-(U5-TX-Pad5)") (class "Default")
      (node (ref "U5") (pin "5") (pinfunction "TX_5") (pintype "passive"))
    )
  )
)
